# BPPower_Management.net
KiCad netlist of a schematic drawn in Altium Designer
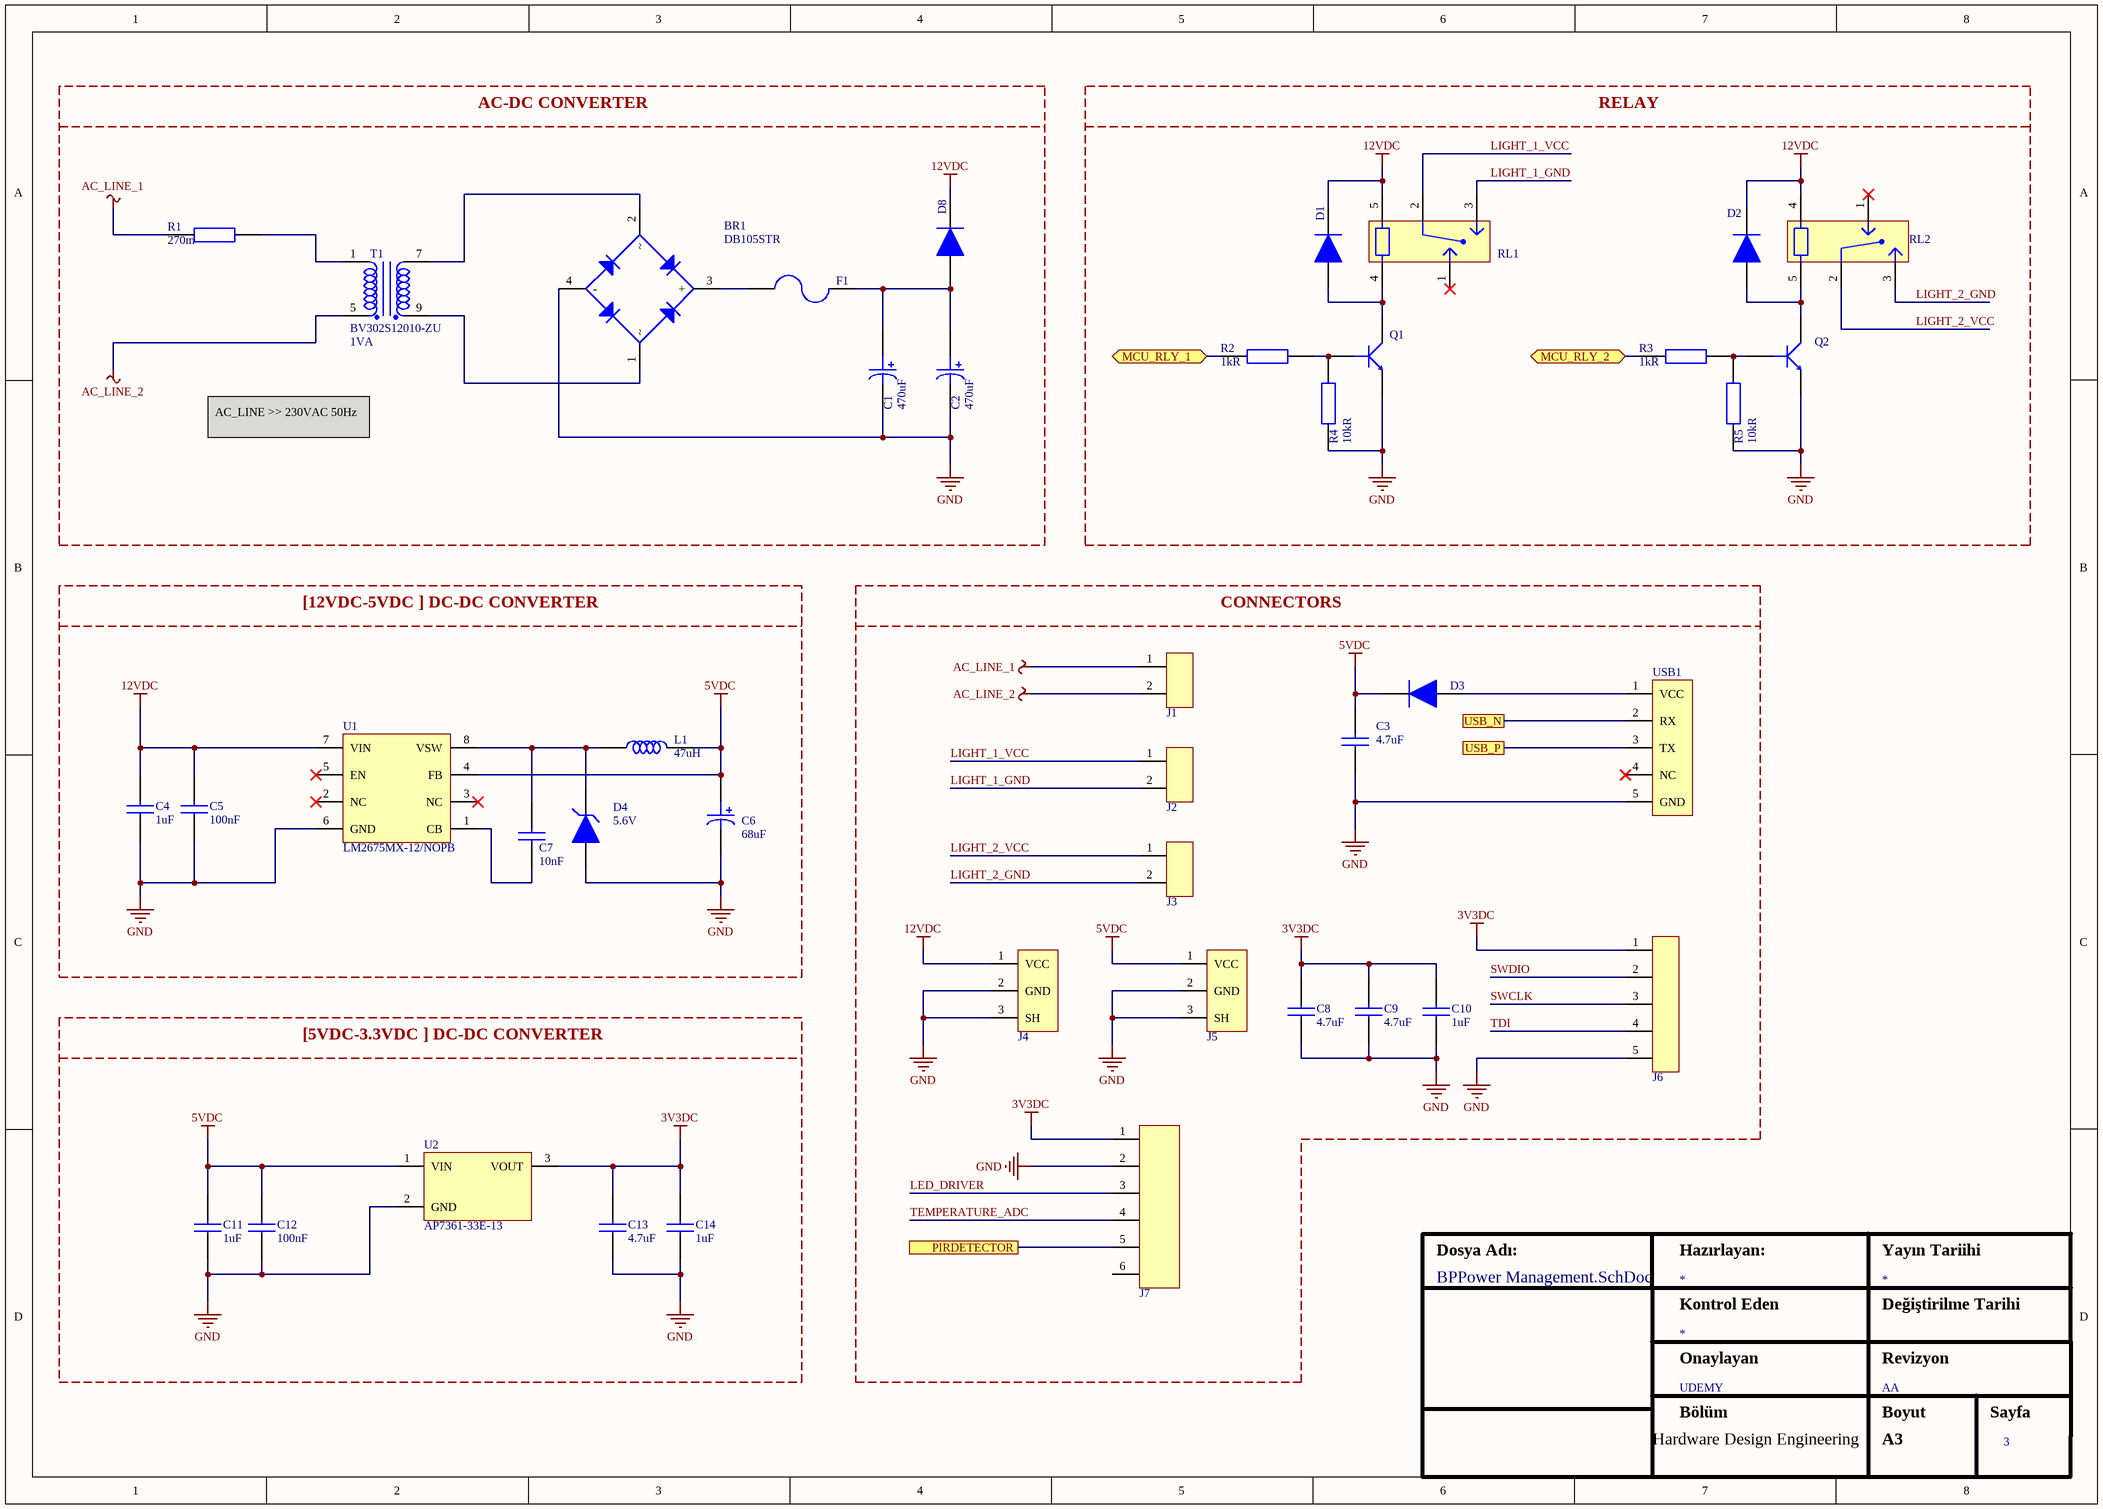
[diagram p0: BPPower Management.SchDoc]

(export (version "E")
  (design (tool "Eeschema 10.0.6"))
  (components
    (comp (ref "BR1")
      (value "DB105STR")
      (footprint "DB105STR")
      (description "Bridge Diode AC-DC")
      (fields (field (name "MANUFACTURER") "Sangdest Microelectronics") (field (name "DESIGNED BY") "BERK"))
      (libsource (lib "UDEMY_Library") (part "DB105STR"))
    )
    (comp (ref "C1")
      (value "ESH477M050AH4AA")
      (footprint "CAP_RADIAL_D10_P5")
      (description "CAP ALU ELEC 470uF 50V RADIAL")
      (fields
        (field (name "MANUFACTURER") "KEMET")
        (field (name "TOLERANCE") "20%")
        (field (name "CAPACITANCE") "470uF")
        (field (name "DESIGNED BY") "BERK")
      )
      (libsource (lib "UDEMY_Library") (part "CAP ALU ELEC 470uF 50V"))
    )
    (comp (ref "C2")
      (value "ESH477M050AH4AA")
      (footprint "CAP_RADIAL_D10_P5")
      (description "CAP ALU ELEC 470uF 50V RADIAL")
      (fields
        (field (name "MANUFACTURER") "KEMET")
        (field (name "TOLERANCE") "20%")
        (field (name "CAPACITANCE") "470uF")
        (field (name "DESIGNED BY") "BERK")
      )
      (libsource (lib "UDEMY_Library") (part "CAP ALU ELEC 470uF 50V"))
    )
    (comp (ref "C3")
      (value "CL21A475KAQNNNE")
      (footprint "CAP_0805")
      (description "CAP CER 4.7uF %10 0805")
      (fields
        (field (name "MANUFACTURER") "Samsung")
        (field (name "TOLERANCE") "10%")
        (field (name "CAPACITANCE") "4.7uF")
        (field (name "DESIGNED BY") "BERK")
      )
      (libsource (lib "UDEMY_Library") (part "CAP CER 4.7uF 0805"))
    )
    (comp (ref "C4")
      (value "CL21B105KBFNNNE")
      (footprint "CAP_0805")
      (description "CAP CER 1uF %10 0805")
      (fields
        (field (name "MANUFACTURER") "Samsung")
        (field (name "TOLERANCE") "10%")
        (field (name "CAPACITANCE") "1uF")
        (field (name "DESIGNED BY") "BERK")
      )
      (libsource (lib "UDEMY_Library") (part "CAP CER 1uF 0805"))
    )
    (comp (ref "C5")
      (value "CL21B104KBCNNNC")
      (footprint "CAP_0805")
      (description "CAP CER 100nF %10 0805")
      (fields
        (field (name "MANUFACTURER") "Samsung")
        (field (name "TOLERANCE") "10%")
        (field (name "CAPACITANCE") "100nF")
        (field (name "DESIGNED BY") "BERK")
      )
      (libsource (lib "UDEMY_Library") (part "CAP CER 100nF 0805"))
    )
    (comp (ref "C6")
      (value "EEV686M035A9HAA")
      (footprint "CAP_EEVseries")
      (description "Cap Aluminum Lytic 68uF 35V 20% (6.3 X 7.7mm) SMD 280mA 2000h 105C T/R")
      (fields
        (field (name "MANUFACTURER") "KEMET")
        (field (name "TOLERANCE") "20%")
        (field (name "CAPACITANCE") "68uF")
      )
      (libsource (lib "UDEMY_Library") (part "CAP ALU 68uF"))
    )
    (comp (ref "C7")
      (value "0603B103K160CT")
      (footprint "CAP_0603")
      (description "CAP CER 10nF %10 0603")
      (fields
        (field (name "MANUFACTURER") "Walsin Technologies")
        (field (name "TOLERANCE") "10%")
        (field (name "CAPACITANCE") "10nF")
        (field (name "DESIGNED BY") "BERK")
      )
      (libsource (lib "UDEMY_Library") (part "CAP CER 10nF 0603"))
    )
    (comp (ref "C8")
      (value "CL21A475KAQNNNE")
      (footprint "CAP_0805")
      (description "CAP CER 4.7uF %10 0805")
      (fields
        (field (name "MANUFACTURER") "Samsung")
        (field (name "TOLERANCE") "10%")
        (field (name "CAPACITANCE") "4.7uF")
        (field (name "DESIGNED BY") "BERK")
      )
      (libsource (lib "UDEMY_Library") (part "CAP CER 4.7uF 0805"))
    )
    (comp (ref "C9")
      (value "CL21A475KAQNNNE")
      (footprint "CAP_0805")
      (description "CAP CER 4.7uF %10 0805")
      (fields
        (field (name "MANUFACTURER") "Samsung")
        (field (name "TOLERANCE") "10%")
        (field (name "CAPACITANCE") "4.7uF")
        (field (name "DESIGNED BY") "BERK")
      )
      (libsource (lib "UDEMY_Library") (part "CAP CER 4.7uF 0805"))
    )
    (comp (ref "C10")
      (value "CL21B105KBFNNNE")
      (footprint "CAP_0805")
      (description "CAP CER 1uF %10 0805")
      (fields
        (field (name "MANUFACTURER") "Samsung")
        (field (name "TOLERANCE") "10%")
        (field (name "CAPACITANCE") "1uF")
        (field (name "DESIGNED BY") "BERK")
      )
      (libsource (lib "UDEMY_Library") (part "CAP CER 1uF 0805"))
    )
    (comp (ref "C11")
      (value "CL21B105KBFNNNE")
      (footprint "CAP_0805")
      (description "CAP CER 1uF %10 0805")
      (fields
        (field (name "MANUFACTURER") "Samsung")
        (field (name "TOLERANCE") "10%")
        (field (name "CAPACITANCE") "1uF")
        (field (name "DESIGNED BY") "BERK")
      )
      (libsource (lib "UDEMY_Library") (part "CAP CER 1uF 0805"))
    )
    (comp (ref "C12")
      (value "C0603C104K5RACTU")
      (footprint "CAP_0603")
      (description "CAP CER 100nF %10 0603 SMD")
      (fields
        (field (name "MANUFACTURER") "KEMET")
        (field (name "TOLERANCE") "10%")
        (field (name "CAPACITANCE") "100nF")
        (field (name "DESIGNED BY") "BERK")
      )
      (libsource (lib "UDEMY_Library") (part "CAP CER 100nF 0603"))
    )
    (comp (ref "C13")
      (value "CL21A475KAQNNNE")
      (footprint "CAP_0805")
      (description "CAP CER 4.7uF %10 0805")
      (fields
        (field (name "MANUFACTURER") "Samsung")
        (field (name "TOLERANCE") "10%")
        (field (name "CAPACITANCE") "4.7uF")
        (field (name "DESIGNED BY") "BERK")
      )
      (libsource (lib "UDEMY_Library") (part "CAP CER 4.7uF 0805"))
    )
    (comp (ref "C14")
      (value "CL21B105KBFNNNE")
      (footprint "CAP_0805")
      (description "CAP CER 1uF %10 0805")
      (fields
        (field (name "MANUFACTURER") "Samsung")
        (field (name "TOLERANCE") "10%")
        (field (name "CAPACITANCE") "1uF")
        (field (name "DESIGNED BY") "BERK")
      )
      (libsource (lib "UDEMY_Library") (part "CAP CER 1uF 0805"))
    )
    (comp (ref "D1")
      (value "1N4148WS")
      (footprint "SOD323F")
      (description "Diode, Single, 75 V, 150 mA, 1 V, 4 ns")
      (fields
        (field (name "MANUFACTURER") "ON Semiconductor / Fairchild")
        (field (name "DESIGNED BY") "BERK")
      )
      (libsource (lib "UDEMY_Library") (part "1N4148WS"))
    )
    (comp (ref "D2")
      (value "1N4148WS")
      (footprint "SOD323F")
      (description "Diode, Single, 75 V, 150 mA, 1 V, 4 ns")
      (fields
        (field (name "MANUFACTURER") "ON Semiconductor / Fairchild")
        (field (name "DESIGNED BY") "BERK")
      )
      (libsource (lib "UDEMY_Library") (part "1N4148WS"))
    )
    (comp (ref "D3")
      (value "1N4148WS")
      (footprint "SOD323F")
      (description "Diode, Single, 75 V, 150 mA, 1 V, 4 ns")
      (fields
        (field (name "MANUFACTURER") "ON Semiconductor / Fairchild")
        (field (name "DESIGNED BY") "BERK")
      )
      (libsource (lib "UDEMY_Library") (part "1N4148WS"))
    )
    (comp (ref "D4")
      (value "1SMB5919BT3G")
      (footprint "SMB")
      (description "Diode Zener Single 5.6V 5% 3W 2-Pin SMB T/R")
      (fields
        (field (name "MANUFACTURER") "ON Semiconductor")
        (field (name "TOLERANCE") "5%")
        (field (name "WORKING VOLTAGE") "5.6V")
        (field (name "DESIGNED BY") "BERK")
      )
      (libsource (lib "UDEMY_Library") (part "1SMB5919BT3G"))
    )
    (comp (ref "D8")
      (value "1N4148WS")
      (footprint "SOD323F")
      (description "Diode, Single, 75 V, 150 mA, 1 V, 4 ns")
      (fields
        (field (name "MANUFACTURER") "ON Semiconductor / Fairchild")
        (field (name "DESIGNED BY") "BERK")
      )
      (libsource (lib "UDEMY_Library") (part "1N4148WS"))
    )
    (comp (ref "F1")
      (value "3413.0216.22")
      (footprint "BPSchematic:3413.0216.22")
      (description "FUSE BRD MNT 1A 32VAC 63VDC 1206")
      (fields (field (name "MANUFACTURER") "Schurter") (field (name "DESIGNED BY") "BERK"))
      (libsource (lib "UDEMY_Library") (part "FUSE 3413.0216.22"))
    )
    (comp (ref "J1")
      (value "TBP01R1-508-02BE")
      (footprint "BPSchematic:TBP01R1-508")
      (description "Conn Shrouded Header HDR 2 POS 5.08mm Solder RA Side Entry Thru-Hole Bag")
      (fields (field (name "MANUFACTURER") "CUI") (field (name "DESIGNED BY") "BERK"))
      (libsource (lib "UDEMY_Library") (part "TBP01R1-508-02BE"))
    )
    (comp (ref "J2")
      (value "TBP01R1-508-02BE")
      (footprint "BPSchematic:TBP01R1-508")
      (description "Conn Shrouded Header HDR 2 POS 5.08mm Solder RA Side Entry Thru-Hole Bag")
      (fields (field (name "MANUFACTURER") "CUI") (field (name "DESIGNED BY") "BERK"))
      (libsource (lib "UDEMY_Library") (part "TBP01R1-508-02BE"))
    )
    (comp (ref "J3")
      (value "TBP01R1-508-02BE")
      (footprint "BPSchematic:TBP01R1-508")
      (description "Conn Shrouded Header HDR 2 POS 5.08mm Solder RA Side Entry Thru-Hole Bag")
      (fields (field (name "MANUFACTURER") "CUI") (field (name "DESIGNED BY") "BERK"))
      (libsource (lib "UDEMY_Library") (part "TBP01R1-508-02BE"))
    )
    (comp (ref "J4")
      (value "PJ-037AH-SMT-TR")
      (footprint "JACK")
      (description "DC Power Connectors Power Jacks")
      (fields (field (name "MANUFACTURER") "CUI") (field (name "DESIGNED BY") "BERK"))
      (libsource (lib "UDEMY_Library") (part "PJ-037AH-SMT-TR"))
    )
    (comp (ref "J5")
      (value "PJ-037AH-SMT-TR")
      (footprint "JACK")
      (description "DC Power Connectors Power Jacks")
      (fields (field (name "MANUFACTURER") "CUI") (field (name "DESIGNED BY") "BERK"))
      (libsource (lib "UDEMY_Library") (part "PJ-037AH-SMT-TR"))
    )
    (comp (ref "J6")
      (value "SMH-105-02-L-S")
      (footprint "PINHEADER1X5_RA")
      (description ".100 C.L. HORIZONTAL SMT SOCKET")
      (fields (field (name "MANUFACTURER") "Samtec") (field (name "DESIGNED BY") "BERK"))
      (libsource (lib "UDEMY_Library") (part "SMH-105-02-L-S"))
    )
    (comp (ref "J7")
      (value "64800611622")
      (footprint "BPSchematic:64800611622")
      (description "1.50mm 6PIN Connector")
      (fields (field (name "MANUFACTURER") "Wurth Electronics"))
      (libsource (lib "UDEMY_Library") (part "64800611622_conn_6pin"))
    )
    (comp (ref "L1")
      (value "78438335470")
      (footprint "IND_1212")
      (description "FIXED IND 47UH 390MA 2.3 OHM SMD")
      (fields
        (field (name "MANUFACTURER") "Wurth Electronics")
        (field (name "TOLERANCE") "30%")
        (field (name "INDUCTANCE") "47uH")
        (field (name "DESIGNED BY") "BERK")
      )
      (libsource (lib "UDEMY_Library") (part "IND 47uH"))
    )
    (comp (ref "Q1")
      (value "MMBT3904-7-F")
      (footprint "SOT-23F")
      (description "Transistor General Purpose BJT NPN 40 Volt 0.2A Automotive 3-Pin SOT-23")
      (fields (field (name "MANUFACTURER") "Diodes Zetex") (field (name "DESIGNED BY") "BERK"))
      (libsource (lib "UDEMY_Library") (part "MMBT3904-7-F"))
    )
    (comp (ref "Q2")
      (value "MMBT3904-7-F")
      (footprint "SOT-23F")
      (description "Transistor General Purpose BJT NPN 40 Volt 0.2A Automotive 3-Pin SOT-23")
      (fields (field (name "MANUFACTURER") "Diodes Zetex") (field (name "DESIGNED BY") "BERK"))
      (libsource (lib "UDEMY_Library") (part "MMBT3904-7-F"))
    )
    (comp (ref "R1")
      (value "5WD27")
      (footprint "RES_AXIAL_W")
      (description "Resistor 5 Watt Cermet Wirewound Flameproof .27 Ohm 5% Axial Lead")
      (fields
        (field (name "MANUFACTURER") "NTE Electronics")
        (field (name "TOLERANCE") "5%")
        (field (name "RESISTANCE") "270m")
        (field (name "DESIGNED BY") "BERK")
      )
      (libsource (lib "UDEMY_Library") (part "5WD27"))
    )
    (comp (ref "R2")
      (value "RC0603FR-0710KL")
      (footprint "RES_0603")
      (description "RES 1K %1 OHM 0603 SMD")
      (fields
        (field (name "MANUFACTURER") "Yageo")
        (field (name "MANUFACTURER PART NUMBER") "RC0603JR-071KL")
        (field (name "RESISTANCE") "1kR")
        (field (name "DESIGNED BY") "BERK")
      )
      (libsource (lib "UDEMY_Library") (part "RES 1K OHM 0603"))
    )
    (comp (ref "R3")
      (value "RC0603FR-0710KL")
      (footprint "RES_0603")
      (description "RES 1K %1 OHM 0603 SMD")
      (fields
        (field (name "MANUFACTURER") "Yageo")
        (field (name "MANUFACTURER PART NUMBER") "RC0603JR-071KL")
        (field (name "RESISTANCE") "1kR")
        (field (name "DESIGNED BY") "BERK")
      )
      (libsource (lib "UDEMY_Library") (part "RES 1K OHM 0603"))
    )
    (comp (ref "R4")
      (value "RC0603FR-0710KL")
      (footprint "RES_0603")
      (description "RES 10K %1 OHM 0603 SMD")
      (fields
        (field (name "MANUFACTURER") "Yageo")
        (field (name "TOLERANCE") "1%")
        (field (name "RESISTANCE") "10kR")
        (field (name "DESIGNED BY") "BERK")
      )
      (libsource (lib "UDEMY_Library") (part "RES 10K OHM 0603"))
    )
    (comp (ref "R5")
      (value "RC0603FR-0710KL")
      (footprint "RES_0603")
      (description "RES 10K %1 OHM 0603 SMD")
      (fields
        (field (name "MANUFACTURER") "Yageo")
        (field (name "TOLERANCE") "1%")
        (field (name "RESISTANCE") "10kR")
        (field (name "DESIGNED BY") "BERK")
      )
      (libsource (lib "UDEMY_Library") (part "RES 10K OHM 0603"))
    )
    (comp (ref "RL1")
      (value "ALQ112")
      (footprint "ALQ112")
      (description "General Purpose Relay SPDT (1 Form C) 12VDC Coil Through Hole")
      (fields (field (name "MANUFACTURER") "Panasonic") (field (name "DESIGNED BY") "BERK"))
      (libsource (lib "") (part "ALQ112_1"))
    )
    (comp (ref "RL2")
      (value "ALQ112")
      (footprint "ALQ112")
      (description "General Purpose Relay SPDT (1 Form C) 12VDC Coil Through Hole")
      (fields (field (name "MANUFACTURER") "Panasonic") (field (name "DESIGNED BY") "BERK"))
      (libsource (lib "UDEMY_Library") (part "ALQ112"))
    )
    (comp (ref "T1")
      (value "BV302S12010-ZU")
      (footprint "BV302S")
      (description "230-12 Transformer 1VA")
      (fields
        (field (name "MANUFACTURER") "Zettler Magnetics")
        (field (name "RATED POWER") "1VA")
        (field (name "DESIGNED BY") "BERK")
      )
      (libsource (lib "UDEMY_Library") (part "BV302S12010-ZU"))
    )
    (comp (ref "U1")
      (value "LM2675MX-12/NOPB")
      (footprint "SOIC8")
      (description "Switching Voltage Regulators Pwr Cnvtr Hi Eff 1A SD Vtg Reg")
      (fields (field (name "MANUFACTURER") "TI National Semiconductor") (field (name "DESIGNED BY") "BERK"))
      (libsource (lib "UDEMY_Library") (part "LM2675MX-12/NOPB"))
    )
    (comp (ref "U2")
      (value "AP7361-33E-13")
      (footprint "SOT223")
      (description "LDO Regulator Pos 3.3V 1A 4-Pin(3+Tab) SOT-223 T/R")
      (fields (field (name "MANUFACTURER") "Diodes") (field (name "DESIGNED BY") "BERK"))
      (libsource (lib "UDEMY_Library") (part "AP7361-33E-13"))
    )
    (comp (ref "USB1")
      (value "10118192-0001LF")
      (footprint "MICRO_B_USB")
      (description "CONN RCPT USB2.0 MICRO B SMD R/A")
      (fields (field (name "MANUFACTURER") "Amphenol FCI") (field (name "DESIGNED BY") "BERK"))
      (libsource (lib "UDEMY_Library") (part "Micro B USB Connector"))
    )
  )
  (nets
    (net (code "1") (name "/LED_DRIVER") (class "Default") (node (ref "J7") (pin "3") (pintype "power_in")))
    (net (code "2") (name "/LIGHT_1_GND") (class "Default")
      (node (ref "J2") (pin "2") (pinfunction "2_2") (pintype "power_in"))
      (node (ref "RL1") (pin "3") (pinfunction "3_3") (pintype "passive"))
    )
    (net (code "3") (name "/LIGHT_1_VCC") (class "Default")
      (node (ref "J2") (pin "1") (pinfunction "1_1") (pintype "power_in"))
      (node (ref "RL1") (pin "2") (pinfunction "2_2") (pintype "passive"))
    )
    (net (code "4") (name "/LIGHT_2_GND") (class "Default")
      (node (ref "J3") (pin "2") (pinfunction "2_2") (pintype "power_in"))
      (node (ref "RL2") (pin "3") (pinfunction "3_3") (pintype "passive"))
    )
    (net (code "5") (name "/LIGHT_2_VCC") (class "Default")
      (node (ref "J3") (pin "1") (pinfunction "1_1") (pintype "power_in"))
      (node (ref "RL2") (pin "2") (pinfunction "2_2") (pintype "passive"))
    )
    (net (code "6") (name "/MCU_RLY_1") (class "Default")
      (node (ref "R2") (pin "1") (pinfunction "1_1") (pintype "passive"))
    )
    (net (code "7") (name "/MCU_RLY_2") (class "Default")
      (node (ref "R3") (pin "1") (pinfunction "1_1") (pintype "passive"))
    )
    (net (code "8") (name "/PIRDETECTOR") (class "Default") (node (ref "J7") (pin "5") (pintype "power_in")))
    (net (code "9") (name "/SWCLK") (class "Default")
      (node (ref "J6") (pin "3") (pinfunction "3_3") (pintype "power_in"))
    )
    (net (code "10") (name "/SWDIO") (class "Default")
      (node (ref "J6") (pin "2") (pinfunction "2_2") (pintype "power_in"))
    )
    (net (code "11") (name "/TDI") (class "Default")
      (node (ref "J6") (pin "4") (pinfunction "4_4") (pintype "power_in"))
    )
    (net (code "12") (name "/TEMPERATURE_ADC") (class "Default")
      (node (ref "J7") (pin "4") (pintype "power_in"))
    )
    (net (code "13") (name "/USB_N") (class "Default")
      (node (ref "USB1") (pin "2") (pinfunction "RX_2") (pintype "power_in"))
    )
    (net (code "14") (name "/USB_P") (class "Default")
      (node (ref "USB1") (pin "3") (pinfunction "TX_3") (pintype "power_in"))
    )
    (net (code "15") (name "3V3DC") (class "Default")
      (node (ref "C10") (pin "2") (pinfunction "2_2") (pintype "passive"))
      (node (ref "C13") (pin "2") (pinfunction "2_2") (pintype "passive"))
      (node (ref "C14") (pin "2") (pinfunction "2_2") (pintype "passive"))
      (node (ref "C8") (pin "2") (pinfunction "2_2") (pintype "passive"))
      (node (ref "C9") (pin "2") (pinfunction "2_2") (pintype "passive"))
      (node (ref "J6") (pin "1") (pinfunction "1_1") (pintype "power_in"))
      (node (ref "J7") (pin "1") (pintype "power_in"))
      (node (ref "U2") (pin "3") (pinfunction "VOUT_3") (pintype "passive"))
    )
    (net (code "16") (name "5VDC") (class "Default")
      (node (ref "C11") (pin "2") (pinfunction "2_2") (pintype "passive"))
      (node (ref "C12") (pin "2") (pinfunction "2_2") (pintype "passive"))
      (node (ref "C3") (pin "2") (pinfunction "2_2") (pintype "passive"))
      (node (ref "C6") (pin "1") (pinfunction "1_1") (pintype "passive"))
      (node (ref "D3") (pin "1") (pinfunction "1_1") (pintype "power_in"))
      (node (ref "J5") (pin "1") (pinfunction "VCC_1") (pintype "power_in"))
      (node (ref "L1") (pin "2") (pinfunction "2_2") (pintype "passive"))
      (node (ref "U1") (pin "4") (pinfunction "FB_4") (pintype "passive"))
      (node (ref "U2") (pin "1") (pinfunction "VIN_1") (pintype "passive"))
    )
    (net (code "17") (name "12VDC") (class "Default")
      (node (ref "C4") (pin "2") (pinfunction "2_2") (pintype "passive"))
      (node (ref "C5") (pin "2") (pinfunction "2_2") (pintype "passive"))
      (node (ref "D1") (pin "1") (pinfunction "1_1") (pintype "power_in"))
      (node (ref "D2") (pin "1") (pinfunction "1_1") (pintype "power_in"))
      (node (ref "D8") (pin "1") (pinfunction "1_1") (pintype "power_in"))
      (node (ref "J4") (pin "1") (pinfunction "VCC_1") (pintype "power_in"))
      (node (ref "RL1") (pin "5") (pinfunction "5_5") (pintype "passive"))
      (node (ref "RL2") (pin "4") (pinfunction "4_4") (pintype "passive"))
      (node (ref "U1") (pin "7") (pinfunction "VIN_7") (pintype "passive"))
    )
    (net (code "18") (name "AC_LINE_1") (class "Default")
      (node (ref "J1") (pin "1") (pinfunction "1_1") (pintype "power_in"))
      (node (ref "R1") (pin "1") (pinfunction "1_1") (pintype "passive"))
    )
    (net (code "19") (name "AC_LINE_2") (class "Default")
      (node (ref "J1") (pin "2") (pinfunction "2_2") (pintype "power_in"))
      (node (ref "T1") (pin "5") (pinfunction "5_5") (pintype "passive"))
    )
    (net (code "20") (name "GND") (class "Default")
      (node (ref "BR1") (pin "4") (pinfunction "-_4") (pintype "passive"))
      (node (ref "C1") (pin "2") (pinfunction "2_2") (pintype "passive"))
      (node (ref "C10") (pin "1") (pinfunction "1_1") (pintype "passive"))
      (node (ref "C11") (pin "1") (pinfunction "1_1") (pintype "passive"))
      (node (ref "C12") (pin "1") (pinfunction "1_1") (pintype "passive"))
      (node (ref "C13") (pin "1") (pinfunction "1_1") (pintype "passive"))
      (node (ref "C14") (pin "1") (pinfunction "1_1") (pintype "passive"))
      (node (ref "C2") (pin "2") (pinfunction "2_2") (pintype "passive"))
      (node (ref "C3") (pin "1") (pinfunction "1_1") (pintype "passive"))
      (node (ref "C4") (pin "1") (pinfunction "1_1") (pintype "passive"))
      (node (ref "C5") (pin "1") (pinfunction "1_1") (pintype "passive"))
      (node (ref "C6") (pin "2") (pinfunction "2_2") (pintype "passive"))
      (node (ref "C8") (pin "1") (pinfunction "1_1") (pintype "passive"))
      (node (ref "C9") (pin "1") (pinfunction "1_1") (pintype "passive"))
      (node (ref "D4") (pin "A") (pinfunction "A_A") (pintype "passive"))
      (node (ref "J4") (pin "2") (pinfunction "GND_2") (pintype "power_in"))
      (node (ref "J4") (pin "3") (pinfunction "SH_3") (pintype "power_in"))
      (node (ref "J5") (pin "2") (pinfunction "GND_2") (pintype "power_in"))
      (node (ref "J5") (pin "3") (pinfunction "SH_3") (pintype "power_in"))
      (node (ref "J6") (pin "5") (pinfunction "5_5") (pintype "power_in"))
      (node (ref "J7") (pin "2") (pintype "power_in"))
      (node (ref "Q1") (pin "2") (pinfunction "E_2") (pintype "power_in"))
      (node (ref "Q2") (pin "2") (pinfunction "E_2") (pintype "power_in"))
      (node (ref "R4") (pin "1") (pinfunction "1_1") (pintype "passive"))
      (node (ref "R5") (pin "1") (pinfunction "1_1") (pintype "passive"))
      (node (ref "U1") (pin "6") (pinfunction "GND_6") (pintype "passive"))
      (node (ref "U2") (pin "2") (pinfunction "GND_2") (pintype "passive"))
      (node (ref "USB1") (pin "5") (pinfunction "GND_5") (pintype "power_in"))
    )
    (net (code "21") (name "Net-(BR1-+)") (class "Default")
      (node (ref "BR1") (pin "3") (pinfunction "+_3") (pintype "passive"))
      (node (ref "F1") (pin "1") (pinfunction "1_1") (pintype "passive"))
    )
    (net (code "22") (name "Net-(BR1-~-Pad1)") (class "Default")
      (node (ref "BR1") (pin "1") (pinfunction "~_1") (pintype "passive"))
      (node (ref "T1") (pin "9") (pinfunction "9_9") (pintype "passive"))
    )
    (net (code "23") (name "Net-(BR1-~-Pad2)") (class "Default")
      (node (ref "BR1") (pin "2") (pinfunction "~_2") (pintype "passive"))
      (node (ref "T1") (pin "7") (pinfunction "7_7") (pintype "passive"))
    )
    (net (code "24") (name "Net-(C1-Pad1)") (class "Default")
      (node (ref "C1") (pin "1") (pinfunction "1_1") (pintype "passive"))
      (node (ref "C2") (pin "1") (pinfunction "1_1") (pintype "passive"))
      (node (ref "D8") (pin "2") (pinfunction "2_2") (pintype "power_in"))
      (node (ref "F1") (pin "2") (pinfunction "2_2") (pintype "passive"))
    )
    (net (code "25") (name "Net-(Q1-B)") (class "Default")
      (node (ref "Q1") (pin "1") (pinfunction "B_1") (pintype "power_in"))
      (node (ref "R2") (pin "2") (pinfunction "2_2") (pintype "passive"))
      (node (ref "R4") (pin "2") (pinfunction "2_2") (pintype "passive"))
    )
    (net (code "26") (name "Net-(Q1-C)") (class "Default")
      (node (ref "D1") (pin "2") (pinfunction "2_2") (pintype "power_in"))
      (node (ref "Q1") (pin "3") (pinfunction "C_3") (pintype "power_in"))
      (node (ref "RL1") (pin "4") (pinfunction "4_4") (pintype "passive"))
    )
    (net (code "27") (name "Net-(Q2-B)") (class "Default")
      (node (ref "Q2") (pin "1") (pinfunction "B_1") (pintype "power_in"))
      (node (ref "R3") (pin "2") (pinfunction "2_2") (pintype "passive"))
      (node (ref "R5") (pin "2") (pinfunction "2_2") (pintype "passive"))
    )
    (net (code "28") (name "Net-(Q2-C)") (class "Default")
      (node (ref "D2") (pin "2") (pinfunction "2_2") (pintype "power_in"))
      (node (ref "Q2") (pin "3") (pinfunction "C_3") (pintype "power_in"))
      (node (ref "RL2") (pin "5") (pinfunction "5_5") (pintype "passive"))
    )
    (net (code "29") (name "Net-(R1-Pad2)") (class "Default")
      (node (ref "R1") (pin "2") (pinfunction "2_2") (pintype "passive"))
      (node (ref "T1") (pin "1") (pinfunction "1_1") (pintype "passive"))
    )
    (net (code "30") (name "Net-(U1-CB)") (class "Default")
      (node (ref "C7") (pin "1") (pinfunction "1_1") (pintype "passive"))
      (node (ref "U1") (pin "1") (pinfunction "CB_1") (pintype "passive"))
    )
    (net (code "31") (name "Net-(U1-VSW)") (class "Default")
      (node (ref "C7") (pin "2") (pinfunction "2_2") (pintype "passive"))
      (node (ref "D4") (pin "C") (pinfunction "C_C") (pintype "passive"))
      (node (ref "L1") (pin "1") (pinfunction "1_1") (pintype "passive"))
      (node (ref "U1") (pin "8") (pinfunction "VSW_8") (pintype "passive"))
    )
    (net (code "32") (name "Net-(USB1-VCC)") (class "Default")
      (node (ref "D3") (pin "2") (pinfunction "2_2") (pintype "power_in"))
      (node (ref "USB1") (pin "1") (pinfunction "VCC_1") (pintype "power_in"))
    )
    (net (code "33") (name "unconnected-(J7-Pad6)") (class "Default")
      (node (ref "J7") (pin "6") (pintype "power_in"))
    )
    (net (code "34") (name "unconnected-(RL1-Pad1)") (class "Default")
      (node (ref "RL1") (pin "1") (pinfunction "1_1") (pintype "passive+no_connect"))
    )
    (net (code "35") (name "unconnected-(RL2-Pad1)") (class "Default")
      (node (ref "RL2") (pin "1") (pinfunction "1_1") (pintype "passive+no_connect"))
    )
    (net (code "36") (name "unconnected-(U1-EN-Pad5)") (class "Default")
      (node (ref "U1") (pin "5") (pinfunction "EN_5") (pintype "passive+no_connect"))
    )
    (net (code "37") (name "unconnected-(U1-NC-Pad2)") (class "Default")
      (node (ref "U1") (pin "2") (pinfunction "NC_2") (pintype "passive+no_connect"))
    )
    (net (code "38") (name "unconnected-(U1-NC-Pad3)") (class "Default")
      (node (ref "U1") (pin "3") (pinfunction "NC_3") (pintype "passive+no_connect"))
    )
    (net (code "39") (name "unconnected-(USB1-NC-Pad4)") (class "Default")
      (node (ref "USB1") (pin "4") (pinfunction "NC_4") (pintype "power_in+no_connect"))
    )
  )
)
